# Sheet1.net
KiCad netlist of a schematic drawn in Altium Designer
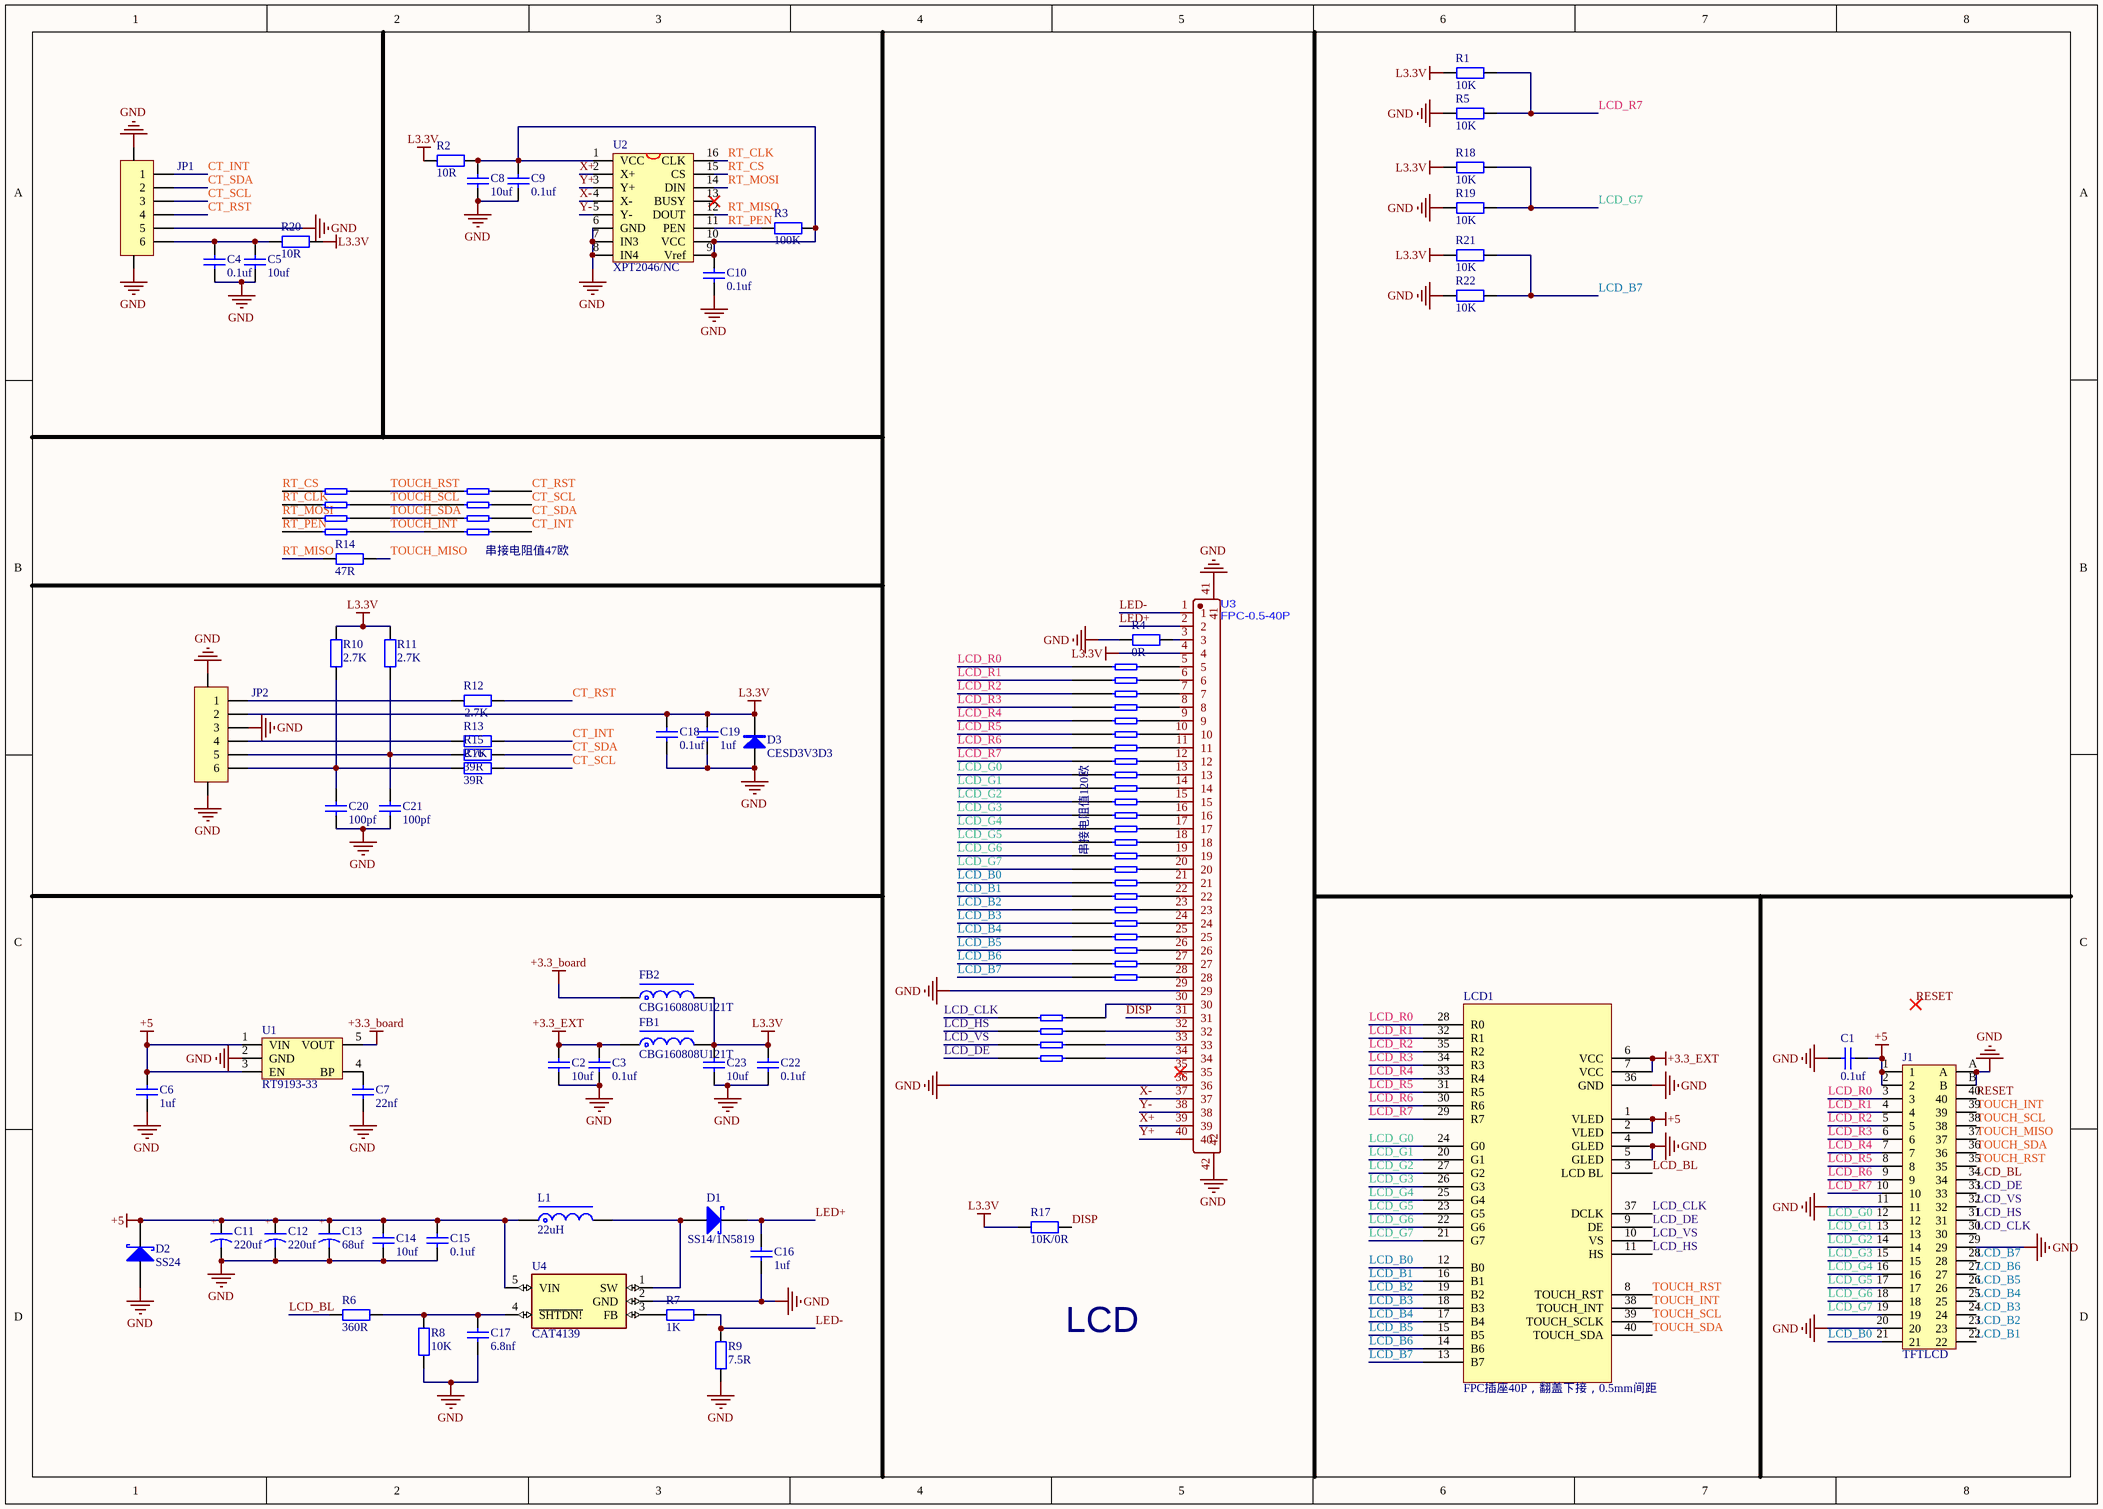
[diagram p0: Sheet1.SchDoc]

(export (version "E")
  (design (tool "Eeschema 10.0.6"))
  (components
    (comp (ref "C1")
      (value "0.1uf")
      (footprint "PCB1:C0603_L")
      (description "贴片电容/MLCC电容")
      (libsource (lib "4.3_RGB_LCD") (part "C"))
    )
    (comp (ref "C2")
      (value "10uf")
      (footprint "PCB1:C0603_L")
      (description "贴片电容/MLCC电容")
      (libsource (lib "4.3_RGB_LCD") (part "C"))
    )
    (comp (ref "C3")
      (value "0.1uf")
      (footprint "PCB1:C0603_L")
      (description "贴片电容/MLCC电容")
      (libsource (lib "4.3_RGB_LCD") (part "C"))
    )
    (comp (ref "C4")
      (value "0.1uf")
      (footprint "PCB1:C0603_L")
      (description "贴片电容/MLCC电容")
      (libsource (lib "4.3_RGB_LCD") (part "C"))
    )
    (comp (ref "C5")
      (value "10uf")
      (footprint "PCB1:C0603_L")
      (description "贴片电容/MLCC电容")
      (libsource (lib "4.3_RGB_LCD") (part "C"))
    )
    (comp (ref "C6")
      (value "1uf")
      (footprint "PCB1:C0603_L")
      (description "贴片电容/MLCC电容")
      (libsource (lib "4.3_RGB_LCD") (part "C"))
    )
    (comp (ref "C7")
      (value "22nf")
      (footprint "PCB1:C0603_L")
      (description "贴片电容/MLCC电容")
      (libsource (lib "4.3_RGB_LCD") (part "C"))
    )
    (comp (ref "C8")
      (value "10uf")
      (footprint "PCB1:C0603_L")
      (description "贴片电容/MLCC电容")
      (libsource (lib "4.3_RGB_LCD") (part "C"))
    )
    (comp (ref "C9")
      (value "0.1uf")
      (footprint "PCB1:C0603_L")
      (description "贴片电容/MLCC电容")
      (libsource (lib "4.3_RGB_LCD") (part "C"))
    )
    (comp (ref "C10")
      (value "0.1uf")
      (footprint "PCB1:C0603_L")
      (description "贴片电容/MLCC电容")
      (libsource (lib "4.3_RGB_LCD") (part "C"))
    )
    (comp (ref "C11")
      (value "220uf")
      (footprint "PCB1:CE A(3*5.4)")
      (description "贴片电解电容")
      (libsource (lib "4.3_RGB_LCD") (part "CE_SMD"))
    )
    (comp (ref "C12")
      (value "220uf")
      (footprint "PCB1:CE A(3*5.4)")
      (description "贴片电解电容")
      (libsource (lib "4.3_RGB_LCD") (part "CE_SMD"))
    )
    (comp (ref "C13")
      (value "68uf")
      (footprint "PCB1:CE A(3*5.4)")
      (description "贴片电解电容")
      (libsource (lib "4.3_RGB_LCD") (part "CE_SMD"))
    )
    (comp (ref "C14")
      (value "10uf")
      (footprint "PCB1:C0603_L")
      (description "贴片电容/MLCC电容")
      (libsource (lib "4.3_RGB_LCD") (part "C"))
    )
    (comp (ref "C15")
      (value "0.1uf")
      (footprint "PCB1:C0603_L")
      (description "贴片电容/MLCC电容")
      (libsource (lib "4.3_RGB_LCD") (part "C"))
    )
    (comp (ref "C16")
      (value "1uf")
      (footprint "PCB1:C0603_L")
      (description "贴片电容/MLCC电容")
      (libsource (lib "4.3_RGB_LCD") (part "C"))
    )
    (comp (ref "C17")
      (value "6.8nf")
      (footprint "PCB1:C0603_L")
      (description "贴片电容/MLCC电容")
      (libsource (lib "4.3_RGB_LCD") (part "C"))
    )
    (comp (ref "C18")
      (value "0.1uf")
      (footprint "PCB1:C0603_L")
      (description "贴片电容/MLCC电容")
      (libsource (lib "4.3_RGB_LCD") (part "C"))
    )
    (comp (ref "C19")
      (value "1uf")
      (footprint "PCB1:C0603_L")
      (description "贴片电容/MLCC电容")
      (libsource (lib "4.3_RGB_LCD") (part "C"))
    )
    (comp (ref "C20")
      (value "100pf")
      (footprint "PCB1:C0603_L")
      (description "贴片电容/MLCC电容")
      (libsource (lib "4.3_RGB_LCD") (part "C"))
    )
    (comp (ref "C21")
      (value "100pf")
      (footprint "PCB1:C0603_L")
      (description "贴片电容/MLCC电容")
      (libsource (lib "4.3_RGB_LCD") (part "C"))
    )
    (comp (ref "C22")
      (value "0.1uf")
      (footprint "PCB1:C0603_L")
      (description "贴片电容/MLCC电容")
      (libsource (lib "4.3_RGB_LCD") (part "C"))
    )
    (comp (ref "C23")
      (value "10uf")
      (footprint "PCB1:C0603_L")
      (description "贴片电容/MLCC电容")
      (libsource (lib "4.3_RGB_LCD") (part "C"))
    )
    (comp (ref "D1")
      (value "SS14/1N5819")
      (footprint "PCB1:SMA")
      (description "肖特基二极管")
      (libsource (lib "4.3_RGB_LCD") (part "SS14"))
    )
    (comp (ref "D2")
      (value "SS24")
      (footprint "PCB1:SMA")
      (description "肖特基二极管")
      (libsource (lib "4.3_RGB_LCD") (part "SS14"))
    )
    (comp (ref "D3")
      (value "CESD3V3D3")
      (footprint "PCB1:SMA")
      (description "整流二极管")
      (libsource (lib "4.3_RGB_LCD") (part "1N4007"))
    )
    (comp (ref "FB1")
      (value "CBG160808U121T")
      (footprint "PCB1:FB0805")
      (description "贴片磁珠")
      (libsource (lib "4.3_RGB_LCD") (part "FB"))
    )
    (comp (ref "FB2")
      (value "CBG160808U121T")
      (footprint "PCB1:FB0805")
      (description "贴片磁珠")
      (libsource (lib "4.3_RGB_LCD") (part "FB"))
    )
    (comp (ref "J1")
      (value "TFTLCD")
      (footprint "PCB1:FPC-TOP40")
      (description "FPC-40P-0.5mm")
      (libsource (lib "4.3_RGB_LCD") (part "FPC-40"))
    )
    (comp (ref "JP1")
      (value "CON-6P")
      (footprint "PCB1:FPC0.5-WT-6P")
      (description "6P连接器")
      (libsource (lib "4.3_RGB_LCD") (part "Header 6"))
    )
    (comp (ref "JP2")
      (value "CON-6P")
      (footprint "PCB1:FPC0.5-WT-6P")
      (description "6P连接器")
      (libsource (lib "4.3_RGB_LCD") (part "Header 6"))
    )
    (comp (ref "L1")
      (value "22uH")
      (footprint "PCB1:L-SMD-0420")
      (description "一体成型电感")
      (libsource (lib "4.3_RGB_LCD") (part "L-Molding Choke"))
    )
    (comp (ref "LCD1")
      (value "FPC插座40P，翻盖下接，0.5mm间距")
      (footprint "PCB1:FPC40P-0.5MM")
      (libsource (lib "4.3_RGB_LCD") (part "MY-RGB"))
    )
    (comp (ref "R1")
      (value "10K")
      (footprint "PCB1:R0603_L")
      (description "贴片电阻")
      (libsource (lib "4.3_RGB_LCD") (part "R"))
    )
    (comp (ref "R2")
      (value "10R")
      (footprint "PCB1:R0603_L")
      (description "贴片电阻")
      (libsource (lib "4.3_RGB_LCD") (part "R"))
    )
    (comp (ref "R3")
      (value "100K")
      (footprint "PCB1:R0603_L")
      (description "贴片电阻")
      (libsource (lib "4.3_RGB_LCD") (part "R"))
    )
    (comp (ref "R4")
      (value "0R")
      (footprint "PCB1:R0603_L")
      (description "贴片电阻")
      (libsource (lib "4.3_RGB_LCD") (part "R"))
    )
    (comp (ref "R5")
      (value "10K")
      (footprint "PCB1:R0603_L")
      (description "贴片电阻")
      (libsource (lib "4.3_RGB_LCD") (part "R"))
    )
    (comp (ref "R6")
      (value "360R")
      (footprint "PCB1:R0603_L")
      (description "贴片电阻")
      (libsource (lib "4.3_RGB_LCD") (part "R"))
    )
    (comp (ref "R7")
      (value "1K")
      (footprint "PCB1:R0603_L")
      (description "贴片电阻")
      (libsource (lib "4.3_RGB_LCD") (part "R"))
    )
    (comp (ref "R8")
      (value "10K")
      (footprint "PCB1:R0603_L")
      (description "贴片电阻")
      (libsource (lib "4.3_RGB_LCD") (part "R"))
    )
    (comp (ref "R9")
      (value "7.5R")
      (footprint "PCB1:R0603_L")
      (description "贴片电阻")
      (libsource (lib "4.3_RGB_LCD") (part "R"))
    )
    (comp (ref "R10")
      (value "2.7K")
      (footprint "PCB1:R0603_L")
      (description "贴片电阻")
      (libsource (lib "4.3_RGB_LCD") (part "R"))
    )
    (comp (ref "R11")
      (value "2.7K")
      (footprint "PCB1:R0603_L")
      (description "贴片电阻")
      (libsource (lib "4.3_RGB_LCD") (part "R"))
    )
    (comp (ref "R12")
      (value "2.7K")
      (footprint "PCB1:R0603_L")
      (description "贴片电阻")
      (libsource (lib "4.3_RGB_LCD") (part "R"))
    )
    (comp (ref "R13")
      (value "2.7K")
      (footprint "PCB1:R0603_L")
      (description "贴片电阻")
      (libsource (lib "4.3_RGB_LCD") (part "R"))
    )
    (comp (ref "R14")
      (value "47R")
      (footprint "PCB1:R0603_L")
      (description "贴片电阻")
      (libsource (lib "4.3_RGB_LCD") (part "R"))
    )
    (comp (ref "R15")
      (value "39R")
      (footprint "PCB1:R0603_L")
      (description "贴片电阻")
      (libsource (lib "4.3_RGB_LCD") (part "R"))
    )
    (comp (ref "R16")
      (value "39R")
      (footprint "PCB1:R0603_L")
      (description "贴片电阻")
      (libsource (lib "4.3_RGB_LCD") (part "R"))
    )
    (comp (ref "R17")
      (value "10K/0R")
      (footprint "PCB1:R0603_L")
      (description "贴片电阻")
      (libsource (lib "4.3_RGB_LCD") (part "R"))
    )
    (comp (ref "R18")
      (value "10K")
      (footprint "PCB1:R0603_L")
      (description "贴片电阻")
      (libsource (lib "4.3_RGB_LCD") (part "R"))
    )
    (comp (ref "R19")
      (value "10K")
      (footprint "PCB1:R0603_L")
      (description "贴片电阻")
      (libsource (lib "4.3_RGB_LCD") (part "R"))
    )
    (comp (ref "R20")
      (value "10R")
      (footprint "PCB1:R0603_L")
      (description "贴片电阻")
      (libsource (lib "4.3_RGB_LCD") (part "R"))
    )
    (comp (ref "R21")
      (value "10K")
      (footprint "PCB1:R0603_L")
      (description "贴片电阻")
      (libsource (lib "4.3_RGB_LCD") (part "R"))
    )
    (comp (ref "R22")
      (value "10K")
      (footprint "PCB1:R0603_L")
      (description "贴片电阻")
      (libsource (lib "4.3_RGB_LCD") (part "R"))
    )
    (comp (ref "RP1")
      (value "120R排阻")
      (footprint "PCB1:0603_4P")
      (libsource (lib "4.3_RGB_LCD") (part "RES_4P"))
    )
    (comp (ref "RP2")
      (value "120R排阻")
      (footprint "PCB1:0603_4P")
      (libsource (lib "4.3_RGB_LCD") (part "RES_4P"))
    )
    (comp (ref "RP3")
      (value "120R排阻")
      (footprint "PCB1:0603_4P")
      (libsource (lib "4.3_RGB_LCD") (part "RES_4P"))
    )
    (comp (ref "RP4")
      (value "120R排阻")
      (footprint "PCB1:0603_4P")
      (libsource (lib "4.3_RGB_LCD") (part "RES_4P"))
    )
    (comp (ref "RP5")
      (value "120R排阻")
      (footprint "PCB1:0603_4P")
      (libsource (lib "4.3_RGB_LCD") (part "RES_4P"))
    )
    (comp (ref "RP6")
      (value "47R排阻")
      (footprint "PCB1:0603_4P")
      (libsource (lib "4.3_RGB_LCD") (part "RES_4P"))
    )
    (comp (ref "RP7")
      (value "47R排阻")
      (footprint "PCB1:0603_4P")
      (libsource (lib "4.3_RGB_LCD") (part "RES_4P"))
    )
    (comp (ref "RP8")
      (value "120R排阻")
      (footprint "PCB1:0603_4P")
      (libsource (lib "4.3_RGB_LCD") (part "RES_4P"))
    )
    (comp (ref "RP9")
      (value "120R排阻")
      (footprint "PCB1:0603_4P")
      (libsource (lib "4.3_RGB_LCD") (part "RES_4P"))
    )
    (comp (ref "U1")
      (value "RT9193-33")
      (footprint "PCB1:SOT-23-5")
      (description "3.3V超低压差LDO")
      (libsource (lib "4.3_RGB_LCD") (part "RT9193-33"))
    )
    (comp (ref "U2")
      (value "XPT2046/NC")
      (footprint "PCB1:SSOP16")
      (libsource (lib "4.3_RGB_LCD") (part "ADS7843"))
    )
    (comp (ref "U3")
      (value "FPC-0.5-40P")
      (footprint "PCB1:CONN-SMD_FPC-0.5-40P")
      (libsource (lib "4.3_RGB_LCD") (part "FPC-0.5-40P"))
    )
    (comp (ref "U4")
      (value "CAT4139")
      (footprint "PCB1:SOT-23(OT)5_LEAD")
      (libsource (lib "4.3_RGB_LCD") (part "CAT4139"))
    )
  )
  (nets
    (net (code "1") (name "+3.3_EXT") (class "Default")
      (node (ref "C2") (pin "2") (pinfunction "2_2") (pintype "passive"))
      (node (ref "C3") (pin "2") (pinfunction "2_2") (pintype "passive"))
      (node (ref "FB1") (pin "1") (pinfunction "1_1") (pintype "passive"))
      (node (ref "LCD1") (pin "6") (pinfunction "VCC_6") (pintype "passive"))
      (node (ref "LCD1") (pin "7") (pinfunction "VCC_7") (pintype "passive"))
    )
    (net (code "2") (name "+3.3_board") (class "Default")
      (node (ref "FB2") (pin "1") (pinfunction "1_1") (pintype "passive"))
      (node (ref "U1") (pin "5") (pinfunction "VOUT_5") (pintype "passive"))
    )
    (net (code "3") (name "+5") (class "Default")
      (node (ref "C1") (pin "1") (pinfunction "1_1") (pintype "passive"))
      (node (ref "C11") (pin "1") (pinfunction "1_1") (pintype "passive"))
      (node (ref "C12") (pin "1") (pinfunction "1_1") (pintype "passive"))
      (node (ref "C13") (pin "1") (pinfunction "1_1") (pintype "passive"))
      (node (ref "C14") (pin "2") (pinfunction "2_2") (pintype "passive"))
      (node (ref "C15") (pin "2") (pinfunction "2_2") (pintype "passive"))
      (node (ref "C6") (pin "2") (pinfunction "2_2") (pintype "passive"))
      (node (ref "D2") (pin "2") (pinfunction "K_2") (pintype "passive"))
      (node (ref "J1") (pin "1") (pinfunction "1_1") (pintype "passive"))
      (node (ref "J1") (pin "2") (pinfunction "2_2") (pintype "passive"))
      (node (ref "L1") (pin "1") (pinfunction "1_1") (pintype "passive"))
      (node (ref "LCD1") (pin "1") (pinfunction "VLED_1") (pintype "passive"))
      (node (ref "LCD1") (pin "2") (pinfunction "VLED_2") (pintype "passive"))
      (node (ref "U1") (pin "1") (pinfunction "VIN_1") (pintype "passive"))
      (node (ref "U1") (pin "3") (pinfunction "EN_3") (pintype "passive"))
      (node (ref "U4") (pin "5") (pinfunction "VIN_5") (pintype "bidirectional"))
    )
    (net (code "4") (name "/CT_INT") (class "Default")
      (node (ref "JP1") (pin "1") (pinfunction "1_1") (pintype "passive"))
      (node (ref "R13") (pin "1") (pinfunction "1_1") (pintype "passive"))
      (node (ref "RP7") (pin "5") (pintype "passive"))
    )
    (net (code "5") (name "/CT_RST") (class "Default")
      (node (ref "JP1") (pin "4") (pinfunction "4_4") (pintype "passive"))
      (node (ref "R12") (pin "1") (pinfunction "1_1") (pintype "passive"))
      (node (ref "RP7") (pin "8") (pintype "passive"))
    )
    (net (code "6") (name "/CT_SCL") (class "Default")
      (node (ref "JP1") (pin "3") (pinfunction "3_3") (pintype "passive"))
      (node (ref "R16") (pin "1") (pinfunction "1_1") (pintype "passive"))
      (node (ref "RP7") (pin "7") (pintype "passive"))
    )
    (net (code "7") (name "/CT_SDA") (class "Default")
      (node (ref "JP1") (pin "2") (pinfunction "2_2") (pintype "passive"))
      (node (ref "R15") (pin "1") (pinfunction "1_1") (pintype "passive"))
      (node (ref "RP7") (pin "6") (pintype "passive"))
    )
    (net (code "8") (name "/DISP") (class "Default")
      (node (ref "R17") (pin "2") (pinfunction "2_2") (pintype "passive"))
      (node (ref "U3") (pin "31") (pinfunction "31_31") (pintype "passive"))
    )
    (net (code "9") (name "/LCD_B0") (class "Default")
      (node (ref "J1") (pin "21") (pinfunction "21_21") (pintype "passive"))
      (node (ref "LCD1") (pin "12") (pinfunction "B0_12") (pintype "passive"))
      (node (ref "RP5") (pin "1") (pintype "passive"))
    )
    (net (code "10") (name "/LCD_B1") (class "Default")
      (node (ref "J1") (pin "22") (pinfunction "22_22") (pintype "passive"))
      (node (ref "LCD1") (pin "16") (pinfunction "B1_16") (pintype "passive"))
      (node (ref "RP5") (pin "2") (pintype "passive"))
    )
    (net (code "11") (name "/LCD_B2") (class "Default")
      (node (ref "J1") (pin "23") (pinfunction "23_23") (pintype "passive"))
      (node (ref "LCD1") (pin "19") (pinfunction "B2_19") (pintype "passive"))
      (node (ref "RP5") (pin "3") (pintype "passive"))
    )
    (net (code "12") (name "/LCD_B3") (class "Default")
      (node (ref "J1") (pin "24") (pinfunction "24_24") (pintype "passive"))
      (node (ref "LCD1") (pin "18") (pinfunction "B3_18") (pintype "passive"))
      (node (ref "RP5") (pin "4") (pintype "passive"))
    )
    (net (code "13") (name "/LCD_B4") (class "Default")
      (node (ref "J1") (pin "25") (pinfunction "25_25") (pintype "passive"))
      (node (ref "LCD1") (pin "17") (pinfunction "B4_17") (pintype "passive"))
      (node (ref "RP8") (pin "1") (pintype "passive"))
    )
    (net (code "14") (name "/LCD_B5") (class "Default")
      (node (ref "J1") (pin "26") (pinfunction "26_26") (pintype "passive"))
      (node (ref "LCD1") (pin "15") (pinfunction "B5_15") (pintype "passive"))
      (node (ref "RP8") (pin "2") (pintype "passive"))
    )
    (net (code "15") (name "/LCD_B6") (class "Default")
      (node (ref "J1") (pin "27") (pinfunction "27_27") (pintype "passive"))
      (node (ref "LCD1") (pin "14") (pinfunction "B6_14") (pintype "passive"))
      (node (ref "RP8") (pin "3") (pintype "passive"))
    )
    (net (code "16") (name "/LCD_B7") (class "Default")
      (node (ref "J1") (pin "28") (pinfunction "28_28") (pintype "passive"))
      (node (ref "LCD1") (pin "13") (pinfunction "B7_13") (pintype "passive"))
      (node (ref "R21") (pin "1") (pinfunction "1_1") (pintype "passive"))
      (node (ref "R22") (pin "1") (pinfunction "1_1") (pintype "passive"))
      (node (ref "RP8") (pin "4") (pintype "passive"))
    )
    (net (code "17") (name "/LCD_BL") (class "Default")
      (node (ref "J1") (pin "34") (pinfunction "34_34") (pintype "passive"))
      (node (ref "LCD1") (pin "3") (pinfunction "LCD_BL_3") (pintype "passive"))
      (node (ref "R6") (pin "2") (pinfunction "2_2") (pintype "passive"))
    )
    (net (code "18") (name "/LCD_CLK") (class "Default")
      (node (ref "J1") (pin "30") (pinfunction "30_30") (pintype "passive"))
      (node (ref "LCD1") (pin "37") (pinfunction "DCLK_37") (pintype "passive"))
      (node (ref "RP9") (pin "1") (pintype "passive"))
    )
    (net (code "19") (name "/LCD_DE") (class "Default")
      (node (ref "J1") (pin "33") (pinfunction "33_33") (pintype "passive"))
      (node (ref "LCD1") (pin "9") (pinfunction "DE_9") (pintype "passive"))
      (node (ref "RP9") (pin "4") (pintype "passive"))
    )
    (net (code "20") (name "/LCD_G0") (class "Default")
      (node (ref "J1") (pin "12") (pinfunction "12_12") (pintype "passive"))
      (node (ref "LCD1") (pin "24") (pinfunction "G0_24") (pintype "passive"))
      (node (ref "RP3") (pin "1") (pintype "passive"))
    )
    (net (code "21") (name "/LCD_G1") (class "Default")
      (node (ref "J1") (pin "13") (pinfunction "13_13") (pintype "passive"))
      (node (ref "LCD1") (pin "20") (pinfunction "G1_20") (pintype "passive"))
      (node (ref "RP3") (pin "2") (pintype "passive"))
    )
    (net (code "22") (name "/LCD_G2") (class "Default")
      (node (ref "J1") (pin "14") (pinfunction "14_14") (pintype "passive"))
      (node (ref "LCD1") (pin "27") (pinfunction "G2_27") (pintype "passive"))
      (node (ref "RP3") (pin "3") (pintype "passive"))
    )
    (net (code "23") (name "/LCD_G3") (class "Default")
      (node (ref "J1") (pin "15") (pinfunction "15_15") (pintype "passive"))
      (node (ref "LCD1") (pin "26") (pinfunction "G3_26") (pintype "passive"))
      (node (ref "RP3") (pin "4") (pintype "passive"))
    )
    (net (code "24") (name "/LCD_G4") (class "Default")
      (node (ref "J1") (pin "16") (pinfunction "16_16") (pintype "passive"))
      (node (ref "LCD1") (pin "25") (pinfunction "G4_25") (pintype "passive"))
      (node (ref "RP4") (pin "1") (pintype "passive"))
    )
    (net (code "25") (name "/LCD_G5") (class "Default")
      (node (ref "J1") (pin "17") (pinfunction "17_17") (pintype "passive"))
      (node (ref "LCD1") (pin "23") (pinfunction "G5_23") (pintype "passive"))
      (node (ref "RP4") (pin "2") (pintype "passive"))
    )
    (net (code "26") (name "/LCD_G6") (class "Default")
      (node (ref "J1") (pin "18") (pinfunction "18_18") (pintype "passive"))
      (node (ref "LCD1") (pin "22") (pinfunction "G6_22") (pintype "passive"))
      (node (ref "RP4") (pin "3") (pintype "passive"))
    )
    (net (code "27") (name "/LCD_G7") (class "Default")
      (node (ref "J1") (pin "19") (pinfunction "19_19") (pintype "passive"))
      (node (ref "LCD1") (pin "21") (pinfunction "G7_21") (pintype "passive"))
      (node (ref "R18") (pin "1") (pinfunction "1_1") (pintype "passive"))
      (node (ref "R19") (pin "1") (pinfunction "1_1") (pintype "passive"))
      (node (ref "RP4") (pin "4") (pintype "passive"))
    )
    (net (code "28") (name "/LCD_HS") (class "Default")
      (node (ref "J1") (pin "31") (pinfunction "31_31") (pintype "passive"))
      (node (ref "LCD1") (pin "11") (pinfunction "HS_11") (pintype "passive"))
      (node (ref "RP9") (pin "2") (pintype "passive"))
    )
    (net (code "29") (name "/LCD_R0") (class "Default")
      (node (ref "J1") (pin "3") (pinfunction "3_3") (pintype "passive"))
      (node (ref "LCD1") (pin "28") (pinfunction "R0_28") (pintype "passive"))
      (node (ref "RP1") (pin "1") (pintype "passive"))
    )
    (net (code "30") (name "/LCD_R1") (class "Default")
      (node (ref "J1") (pin "4") (pinfunction "4_4") (pintype "passive"))
      (node (ref "LCD1") (pin "32") (pinfunction "R1_32") (pintype "passive"))
      (node (ref "RP1") (pin "2") (pintype "passive"))
    )
    (net (code "31") (name "/LCD_R2") (class "Default")
      (node (ref "J1") (pin "5") (pinfunction "5_5") (pintype "passive"))
      (node (ref "LCD1") (pin "35") (pinfunction "R2_35") (pintype "passive"))
      (node (ref "RP1") (pin "3") (pintype "passive"))
    )
    (net (code "32") (name "/LCD_R3") (class "Default")
      (node (ref "J1") (pin "6") (pinfunction "6_6") (pintype "passive"))
      (node (ref "LCD1") (pin "34") (pinfunction "R3_34") (pintype "passive"))
      (node (ref "RP1") (pin "4") (pintype "passive"))
    )
    (net (code "33") (name "/LCD_R4") (class "Default")
      (node (ref "J1") (pin "7") (pinfunction "7_7") (pintype "passive"))
      (node (ref "LCD1") (pin "33") (pinfunction "R4_33") (pintype "passive"))
      (node (ref "RP2") (pin "1") (pintype "passive"))
    )
    (net (code "34") (name "/LCD_R5") (class "Default")
      (node (ref "J1") (pin "8") (pinfunction "8_8") (pintype "passive"))
      (node (ref "LCD1") (pin "31") (pinfunction "R5_31") (pintype "passive"))
      (node (ref "RP2") (pin "2") (pintype "passive"))
    )
    (net (code "35") (name "/LCD_R6") (class "Default")
      (node (ref "J1") (pin "9") (pinfunction "9_9") (pintype "passive"))
      (node (ref "LCD1") (pin "30") (pinfunction "R6_30") (pintype "passive"))
      (node (ref "RP2") (pin "3") (pintype "passive"))
    )
    (net (code "36") (name "/LCD_R7") (class "Default")
      (node (ref "J1") (pin "10") (pinfunction "10_10") (pintype "passive"))
      (node (ref "LCD1") (pin "29") (pinfunction "R7_29") (pintype "passive"))
      (node (ref "R1") (pin "1") (pinfunction "1_1") (pintype "passive"))
      (node (ref "R5") (pin "1") (pinfunction "1_1") (pintype "passive"))
      (node (ref "RP2") (pin "4") (pintype "passive"))
    )
    (net (code "37") (name "/LCD_VS") (class "Default")
      (node (ref "J1") (pin "32") (pinfunction "32_32") (pintype "passive"))
      (node (ref "LCD1") (pin "10") (pinfunction "VS_10") (pintype "passive"))
      (node (ref "RP9") (pin "3") (pintype "passive"))
    )
    (net (code "38") (name "/LED+") (class "Default")
      (node (ref "C16") (pin "2") (pinfunction "2_2") (pintype "passive"))
      (node (ref "D1") (pin "2") (pinfunction "K_2") (pintype "passive"))
      (node (ref "U3") (pin "2") (pinfunction "2_2") (pintype "passive"))
    )
    (net (code "39") (name "/LED-") (class "Default")
      (node (ref "R7") (pin "1") (pinfunction "1_1") (pintype "passive"))
      (node (ref "R9") (pin "1") (pinfunction "1_1") (pintype "passive"))
      (node (ref "U3") (pin "1") (pinfunction "1_1") (pintype "passive"))
    )
    (net (code "40") (name "/RESET") (class "Default")
      (node (ref "J1") (pin "40") (pinfunction "40_40") (pintype "passive+no_connect"))
    )
    (net (code "41") (name "/RT_CLK") (class "Default")
      (node (ref "RP6") (pin "2") (pintype "passive"))
      (node (ref "U2") (pin "16") (pinfunction "CLK_16") (pintype "passive"))
    )
    (net (code "42") (name "/RT_CS") (class "Default")
      (node (ref "RP6") (pin "1") (pintype "passive"))
      (node (ref "U2") (pin "15") (pinfunction "CS_15") (pintype "passive"))
    )
    (net (code "43") (name "/RT_MISO") (class "Default")
      (node (ref "R14") (pin "2") (pinfunction "2_2") (pintype "passive"))
      (node (ref "U2") (pin "12") (pinfunction "DOUT_12") (pintype "passive"))
    )
    (net (code "44") (name "/RT_MOSI") (class "Default")
      (node (ref "RP6") (pin "3") (pintype "passive"))
      (node (ref "U2") (pin "14") (pinfunction "DIN_14") (pintype "passive"))
    )
    (net (code "45") (name "/RT_PEN") (class "Default")
      (node (ref "R3") (pin "2") (pinfunction "2_2") (pintype "passive"))
      (node (ref "RP6") (pin "4") (pintype "passive"))
      (node (ref "U2") (pin "11") (pinfunction "PEN_11") (pintype "passive"))
    )
    (net (code "46") (name "/TOUCH_INT") (class "Default")
      (node (ref "J1") (pin "39") (pinfunction "39_39") (pintype "passive"))
      (node (ref "LCD1") (pin "38") (pinfunction "TOUCH_INT_38") (pintype "passive"))
      (node (ref "RP6") (pin "5") (pintype "passive"))
      (node (ref "RP7") (pin "4") (pintype "passive"))
    )
    (net (code "47") (name "/TOUCH_MISO") (class "Default")
      (node (ref "J1") (pin "37") (pinfunction "37_37") (pintype "passive"))
      (node (ref "R14") (pin "1") (pinfunction "1_1") (pintype "passive"))
    )
    (net (code "48") (name "/TOUCH_RST") (class "Default")
      (node (ref "J1") (pin "35") (pinfunction "35_35") (pintype "passive"))
      (node (ref "LCD1") (pin "8") (pinfunction "TOUCH_RST_8") (pintype "passive"))
      (node (ref "RP6") (pin "8") (pintype "passive"))
      (node (ref "RP7") (pin "1") (pintype "passive"))
    )
    (net (code "49") (name "/TOUCH_SCL") (class "Default")
      (node (ref "J1") (pin "38") (pinfunction "38_38") (pintype "passive"))
      (node (ref "LCD1") (pin "39") (pinfunction "TOUCH_SCLK_39") (pintype "passive"))
      (node (ref "RP6") (pin "7") (pintype "passive"))
      (node (ref "RP7") (pin "2") (pintype "passive"))
    )
    (net (code "50") (name "/TOUCH_SDA") (class "Default")
      (node (ref "J1") (pin "36") (pinfunction "36_36") (pintype "passive"))
      (node (ref "LCD1") (pin "40") (pinfunction "TOUCH_SDA_40") (pintype "passive"))
      (node (ref "RP6") (pin "6") (pintype "passive"))
      (node (ref "RP7") (pin "3") (pintype "passive"))
    )
    (net (code "51") (name "/X+") (class "Default")
      (node (ref "U2") (pin "2") (pinfunction "X+_2") (pintype "passive"))
      (node (ref "U3") (pin "39") (pinfunction "39_39") (pintype "passive"))
    )
    (net (code "52") (name "/X-") (class "Default")
      (node (ref "U2") (pin "4") (pinfunction "X-_4") (pintype "passive"))
      (node (ref "U3") (pin "37") (pinfunction "37_37") (pintype "passive"))
    )
    (net (code "53") (name "/Y+") (class "Default")
      (node (ref "U2") (pin "3") (pinfunction "Y+_3") (pintype "passive"))
      (node (ref "U3") (pin "40") (pinfunction "40_40") (pintype "passive"))
    )
    (net (code "54") (name "/Y-") (class "Default")
      (node (ref "U2") (pin "5") (pinfunction "Y-_5") (pintype "passive"))
      (node (ref "U3") (pin "38") (pinfunction "38_38") (pintype "passive"))
    )
    (net (code "55") (name "GND") (class "Default")
      (node (ref "C1") (pin "2") (pinfunction "2_2") (pintype "passive"))
      (node (ref "C10") (pin "1") (pinfunction "1_1") (pintype "passive"))
      (node (ref "C11") (pin "2") (pinfunction "2_2") (pintype "passive"))
      (node (ref "C12") (pin "2") (pinfunction "2_2") (pintype "passive"))
      (node (ref "C13") (pin "2") (pinfunction "2_2") (pintype "passive"))
      (node (ref "C14") (pin "1") (pinfunction "1_1") (pintype "passive"))
      (node (ref "C15") (pin "1") (pinfunction "1_1") (pintype "passive"))
      (node (ref "C16") (pin "1") (pinfunction "1_1") (pintype "passive"))
      (node (ref "C17") (pin "1") (pinfunction "1_1") (pintype "passive"))
      (node (ref "C18") (pin "1") (pinfunction "1_1") (pintype "passive"))
      (node (ref "C19") (pin "1") (pinfunction "1_1") (pintype "passive"))
      (node (ref "C2") (pin "1") (pinfunction "1_1") (pintype "passive"))
      (node (ref "C20") (pin "1") (pinfunction "1_1") (pintype "passive"))
      (node (ref "C21") (pin "1") (pinfunction "1_1") (pintype "passive"))
      (node (ref "C22") (pin "1") (pinfunction "1_1") (pintype "passive"))
      (node (ref "C23") (pin "1") (pinfunction "1_1") (pintype "passive"))
      (node (ref "C3") (pin "1") (pinfunction "1_1") (pintype "passive"))
      (node (ref "C4") (pin "1") (pinfunction "1_1") (pintype "passive"))
      (node (ref "C5") (pin "1") (pinfunction "1_1") (pintype "passive"))
      (node (ref "C6") (pin "1") (pinfunction "1_1") (pintype "passive"))
      (node (ref "C7") (pin "1") (pinfunction "1_1") (pintype "passive"))
      (node (ref "C8") (pin "1") (pinfunction "1_1") (pintype "passive"))
      (node (ref "C9") (pin "1") (pinfunction "1_1") (pintype "passive"))
      (node (ref "D2") (pin "1") (pinfunction "A_1") (pintype "passive"))
      (node (ref "D3") (pin "1") (pinfunction "A_1") (pintype "passive"))
      (node (ref "J1") (pin "11") (pinfunction "11_11") (pintype "passive"))
      (node (ref "J1") (pin "20") (pinfunction "20_20") (pintype "passive"))
      (node (ref "J1") (pin "29") (pinfunction "29_29") (pintype "passive"))
      (node (ref "J1") (pin "A") (pinfunction "A_A") (pintype "passive"))
      (node (ref "J1") (pin "B") (pinfunction "B_B") (pintype "passive"))
      (node (ref "JP1") (pin "0") (pinfunction "0_0") (pintype "passive"))
      (node (ref "JP1") (pin "5") (pinfunction "5_5") (pintype "passive"))
      (node (ref "JP2") (pin "0") (pinfunction "0_0") (pintype "passive"))
      (node (ref "JP2") (pin "3") (pinfunction "3_3") (pintype "passive"))
      (node (ref "LCD1") (pin "36") (pinfunction "GND_36") (pintype "passive"))
      (node (ref "LCD1") (pin "4") (pinfunction "GLED_4") (pintype "passive"))
      (node (ref "LCD1") (pin "5") (pinfunction "GLED_5") (pintype "passive"))
      (node (ref "R19") (pin "2") (pinfunction "2_2") (pintype "passive"))
      (node (ref "R22") (pin "2") (pinfunction "2_2") (pintype "passive"))
      (node (ref "R4") (pin "2") (pinfunction "2_2") (pintype "passive"))
      (node (ref "R5") (pin "2") (pinfunction "2_2") (pintype "passive"))
      (node (ref "R8") (pin "2") (pinfunction "2_2") (pintype "passive"))
      (node (ref "R9") (pin "2") (pinfunction "2_2") (pintype "passive"))
      (node (ref "U1") (pin "2") (pinfunction "GND_2") (pintype "passive"))
      (node (ref "U2") (pin "6") (pinfunction "GND_6") (pintype "passive"))
      (node (ref "U2") (pin "7") (pinfunction "IN3_7") (pintype "passive"))
      (node (ref "U2") (pin "8") (pinfunction "IN4_8") (pintype "passive"))
      (node (ref "U3") (pin "29") (pinfunction "29_29") (pintype "passive"))
      (node (ref "U3") (pin "36") (pinfunction "36_36") (pintype "passive"))
      (node (ref "U3") (pin "41") (pinfunction "41_41") (pintype "passive"))
      (node (ref "U3") (pin "42") (pinfunction "42_42") (pintype "passive"))
      (node (ref "U4") (pin "2") (pinfunction "GND_2") (pintype "bidirectional"))
    )
    (net (code "56") (name "L3.3V") (class "Default")
      (node (ref "C18") (pin "2") (pinfunction "2_2") (pintype "passive"))
      (node (ref "C19") (pin "2") (pinfunction "2_2") (pintype "passive"))
      (node (ref "C22") (pin "2") (pinfunction "2_2") (pintype "passive"))
      (node (ref "C23") (pin "2") (pinfunction "2_2") (pintype "passive"))
      (node (ref "D3") (pin "2") (pinfunction "K_2") (pintype "passive"))
      (node (ref "FB1") (pin "2") (pinfunction "2_2") (pintype "passive"))
      (node (ref "FB2") (pin "2") (pinfunction "2_2") (pintype "passive"))
      (node (ref "JP2") (pin "2") (pinfunction "2_2") (pintype "passive"))
      (node (ref "R1") (pin "2") (pinfunction "2_2") (pintype "passive"))
      (node (ref "R10") (pin "2") (pinfunction "2_2") (pintype "passive"))
      (node (ref "R11") (pin "2") (pinfunction "2_2") (pintype "passive"))
      (node (ref "R17") (pin "1") (pinfunction "1_1") (pintype "passive"))
      (node (ref "R18") (pin "2") (pinfunction "2_2") (pintype "passive"))
      (node (ref "R2") (pin "2") (pinfunction "2_2") (pintype "passive"))
      (node (ref "R20") (pin "1") (pinfunction "1_1") (pintype "passive"))
      (node (ref "R21") (pin "2") (pinfunction "2_2") (pintype "passive"))
      (node (ref "U3") (pin "4") (pinfunction "4_4") (pintype "passive"))
    )
    (net (code "57") (name "Net-(C4-Pad2)") (class "Default")
      (node (ref "C4") (pin "2") (pinfunction "2_2") (pintype "passive"))
      (node (ref "C5") (pin "2") (pinfunction "2_2") (pintype "passive"))
      (node (ref "JP1") (pin "6") (pinfunction "6_6") (pintype "passive"))
      (node (ref "R20") (pin "2") (pinfunction "2_2") (pintype "passive"))
    )
    (net (code "58") (name "Net-(C20-Pad2)") (class "Default")
      (node (ref "C20") (pin "2") (pinfunction "2_2") (pintype "passive"))
      (node (ref "JP2") (pin "6") (pinfunction "6_6") (pintype "passive"))
      (node (ref "R10") (pin "1") (pinfunction "1_1") (pintype "passive"))
      (node (ref "R16") (pin "2") (pinfunction "2_2") (pintype "passive"))
    )
    (net (code "59") (name "Net-(C21-Pad2)") (class "Default")
      (node (ref "C21") (pin "2") (pinfunction "2_2") (pintype "passive"))
      (node (ref "JP2") (pin "5") (pinfunction "5_5") (pintype "passive"))
      (node (ref "R11") (pin "1") (pinfunction "1_1") (pintype "passive"))
      (node (ref "R15") (pin "2") (pinfunction "2_2") (pintype "passive"))
    )
    (net (code "60") (name "Net-(D1-A)") (class "Default")
      (node (ref "D1") (pin "1") (pinfunction "A_1") (pintype "passive"))
      (node (ref "L1") (pin "2") (pinfunction "2_2") (pintype "passive"))
      (node (ref "U4") (pin "1") (pinfunction "SW_1") (pintype "bidirectional"))
    )
    (net (code "61") (name "Net-(JP2-Pad1)") (class "Default")
      (node (ref "JP2") (pin "1") (pinfunction "1_1") (pintype "passive"))
      (node (ref "R12") (pin "2") (pinfunction "2_2") (pintype "passive"))
    )
    (net (code "62") (name "Net-(JP2-Pad4)") (class "Default")
      (node (ref "JP2") (pin "4") (pinfunction "4_4") (pintype "passive"))
      (node (ref "R13") (pin "2") (pinfunction "2_2") (pintype "passive"))
    )
    (net (code "63") (name "Net-(R4-Pad1)") (class "Default")
      (node (ref "R4") (pin "1") (pinfunction "1_1") (pintype "passive"))
      (node (ref "U3") (pin "3") (pinfunction "3_3") (pintype "passive"))
    )
    (net (code "64") (name "Net-(RP1-Pad5)") (class "Default")
      (node (ref "RP1") (pin "5") (pintype "passive"))
      (node (ref "U3") (pin "8") (pinfunction "8_8") (pintype "passive"))
    )
    (net (code "65") (name "Net-(RP1-Pad6)") (class "Default")
      (node (ref "RP1") (pin "6") (pintype "passive"))
      (node (ref "U3") (pin "7") (pinfunction "7_7") (pintype "passive"))
    )
    (net (code "66") (name "Net-(RP1-Pad7)") (class "Default")
      (node (ref "RP1") (pin "7") (pintype "passive"))
      (node (ref "U3") (pin "6") (pinfunction "6_6") (pintype "passive"))
    )
    (net (code "67") (name "Net-(RP1-Pad8)") (class "Default")
      (node (ref "RP1") (pin "8") (pintype "passive"))
      (node (ref "U3") (pin "5") (pinfunction "5_5") (pintype "passive"))
    )
    (net (code "68") (name "Net-(RP2-Pad5)") (class "Default")
      (node (ref "RP2") (pin "5") (pintype "passive"))
      (node (ref "U3") (pin "12") (pinfunction "12_12") (pintype "passive"))
    )
    (net (code "69") (name "Net-(RP2-Pad6)") (class "Default")
      (node (ref "RP2") (pin "6") (pintype "passive"))
      (node (ref "U3") (pin "11") (pinfunction "11_11") (pintype "passive"))
    )
    (net (code "70") (name "Net-(RP2-Pad7)") (class "Default")
      (node (ref "RP2") (pin "7") (pintype "passive"))
      (node (ref "U3") (pin "10") (pinfunction "10_10") (pintype "passive"))
    )
    (net (code "71") (name "Net-(RP2-Pad8)") (class "Default")
      (node (ref "RP2") (pin "8") (pintype "passive"))
      (node (ref "U3") (pin "9") (pinfunction "9_9") (pintype "passive"))
    )
    (net (code "72") (name "Net-(RP3-Pad5)") (class "Default")
      (node (ref "RP3") (pin "5") (pintype "passive"))
      (node (ref "U3") (pin "16") (pinfunction "16_16") (pintype "passive"))
    )
    (net (code "73") (name "Net-(RP3-Pad6)") (class "Default")
      (node (ref "RP3") (pin "6") (pintype "passive"))
      (node (ref "U3") (pin "15") (pinfunction "15_15") (pintype "passive"))
    )
    (net (code "74") (name "Net-(RP3-Pad7)") (class "Default")
      (node (ref "RP3") (pin "7") (pintype "passive"))
      (node (ref "U3") (pin "14") (pinfunction "14_14") (pintype "passive"))
    )
    (net (code "75") (name "Net-(RP3-Pad8)") (class "Default")
      (node (ref "RP3") (pin "8") (pintype "passive"))
      (node (ref "U3") (pin "13") (pinfunction "13_13") (pintype "passive"))
    )
    (net (code "76") (name "Net-(RP4-Pad5)") (class "Default")
      (node (ref "RP4") (pin "5") (pintype "passive"))
      (node (ref "U3") (pin "20") (pinfunction "20_20") (pintype "passive"))
    )
    (net (code "77") (name "Net-(RP4-Pad6)") (class "Default")
      (node (ref "RP4") (pin "6") (pintype "passive"))
      (node (ref "U3") (pin "19") (pinfunction "19_19") (pintype "passive"))
    )
    (net (code "78") (name "Net-(RP4-Pad7)") (class "Default")
      (node (ref "RP4") (pin "7") (pintype "passive"))
      (node (ref "U3") (pin "18") (pinfunction "18_18") (pintype "passive"))
    )
    (net (code "79") (name "Net-(RP4-Pad8)") (class "Default")
      (node (ref "RP4") (pin "8") (pintype "passive"))
      (node (ref "U3") (pin "17") (pinfunction "17_17") (pintype "passive"))
    )
    (net (code "80") (name "Net-(RP5-Pad5)") (class "Default")
      (node (ref "RP5") (pin "5") (pintype "passive"))
      (node (ref "U3") (pin "24") (pinfunction "24_24") (pintype "passive"))
    )
    (net (code "81") (name "Net-(RP5-Pad6)") (class "Default")
      (node (ref "RP5") (pin "6") (pintype "passive"))
      (node (ref "U3") (pin "23") (pinfunction "23_23") (pintype "passive"))
    )
    (net (code "82") (name "Net-(RP5-Pad7)") (class "Default")
      (node (ref "RP5") (pin "7") (pintype "passive"))
      (node (ref "U3") (pin "22") (pinfunction "22_22") (pintype "passive"))
    )
    (net (code "83") (name "Net-(RP5-Pad8)") (class "Default")
      (node (ref "RP5") (pin "8") (pintype "passive"))
      (node (ref "U3") (pin "21") (pinfunction "21_21") (pintype "passive"))
    )
    (net (code "84") (name "Net-(RP8-Pad5)") (class "Default")
      (node (ref "RP8") (pin "5") (pintype "passive"))
      (node (ref "U3") (pin "28") (pinfunction "28_28") (pintype "passive"))
    )
    (net (code "85") (name "Net-(RP8-Pad6)") (class "Default")
      (node (ref "RP8") (pin "6") (pintype "passive"))
      (node (ref "U3") (pin "27") (pinfunction "27_27") (pintype "passive"))
    )
    (net (code "86") (name "Net-(RP8-Pad7)") (class "Default")
      (node (ref "RP8") (pin "7") (pintype "passive"))
      (node (ref "U3") (pin "26") (pinfunction "26_26") (pintype "passive"))
    )
    (net (code "87") (name "Net-(RP8-Pad8)") (class "Default")
      (node (ref "RP8") (pin "8") (pintype "passive"))
      (node (ref "U3") (pin "25") (pinfunction "25_25") (pintype "passive"))
    )
    (net (code "88") (name "Net-(RP9-Pad5)") (class "Default")
      (node (ref "RP9") (pin "5") (pintype "passive"))
      (node (ref "U3") (pin "34") (pinfunction "34_34") (pintype "passive"))
    )
    (net (code "89") (name "Net-(RP9-Pad6)") (class "Default")
      (node (ref "RP9") (pin "6") (pintype "passive"))
      (node (ref "U3") (pin "33") (pinfunction "33_33") (pintype "passive"))
    )
    (net (code "90") (name "Net-(RP9-Pad7)") (class "Default")
      (node (ref "RP9") (pin "7") (pintype "passive"))
      (node (ref "U3") (pin "32") (pinfunction "32_32") (pintype "passive"))
    )
    (net (code "91") (name "Net-(RP9-Pad8)") (class "Default")
      (node (ref "RP9") (pin "8") (pintype "passive"))
      (node (ref "U3") (pin "30") (pinfunction "30_30") (pintype "passive"))
    )
    (net (code "92") (name "Net-(U1-BP)") (class "Default")
      (node (ref "C7") (pin "2") (pinfunction "2_2") (pintype "passive"))
      (node (ref "U1") (pin "4") (pinfunction "BP_4") (pintype "passive"))
    )
    (net (code "93") (name "Net-(U2-Vref)") (class "Default")
      (node (ref "C10") (pin "2") (pinfunction "2_2") (pintype "passive"))
      (node (ref "C8") (pin "2") (pinfunction "2_2") (pintype "passive"))
      (node (ref "C9") (pin "2") (pinfunction "2_2") (pintype "passive"))
      (node (ref "R2") (pin "1") (pinfunction "1_1") (pintype "passive"))
      (node (ref "R3") (pin "1") (pinfunction "1_1") (pintype "passive"))
      (node (ref "U2") (pin "1") (pinfunction "VCC_1") (pintype "passive"))
      (node (ref "U2") (pin "10") (pinfunction "VCC_10") (pintype "passive"))
      (node (ref "U2") (pin "9") (pinfunction "Vref_9") (pintype "passive"))
    )
    (net (code "94") (name "Net-(U4-FB)") (class "Default")
      (node (ref "R7") (pin "2") (pinfunction "2_2") (pintype "passive"))
      (node (ref "U4") (pin "3") (pinfunction "FB_3") (pintype "bidirectional"))
    )
    (net (code "95") (name "Net-(U4-~{SHTDN!})") (class "Default")
      (node (ref "C17") (pin "2") (pinfunction "2_2") (pintype "passive"))
      (node (ref "R6") (pin "1") (pinfunction "1_1") (pintype "passive"))
      (node (ref "R8") (pin "1") (pinfunction "1_1") (pintype "passive"))
      (node (ref "U4") (pin "4") (pinfunction "~{SHTDN!}_4") (pintype "bidirectional"))
    )
    (net (code "96") (name "unconnected-(U2-BUSY-Pad13)") (class "Default")
      (node (ref "U2") (pin "13") (pinfunction "BUSY_13") (pintype "passive+no_connect"))
    )
    (net (code "97") (name "unconnected-(U3-Pad35)") (class "Default")
      (node (ref "U3") (pin "35") (pinfunction "35_35") (pintype "passive+no_connect"))
    )
  )
)
